# Sheet2.net
KiCad netlist of a schematic drawn in Altium Designer
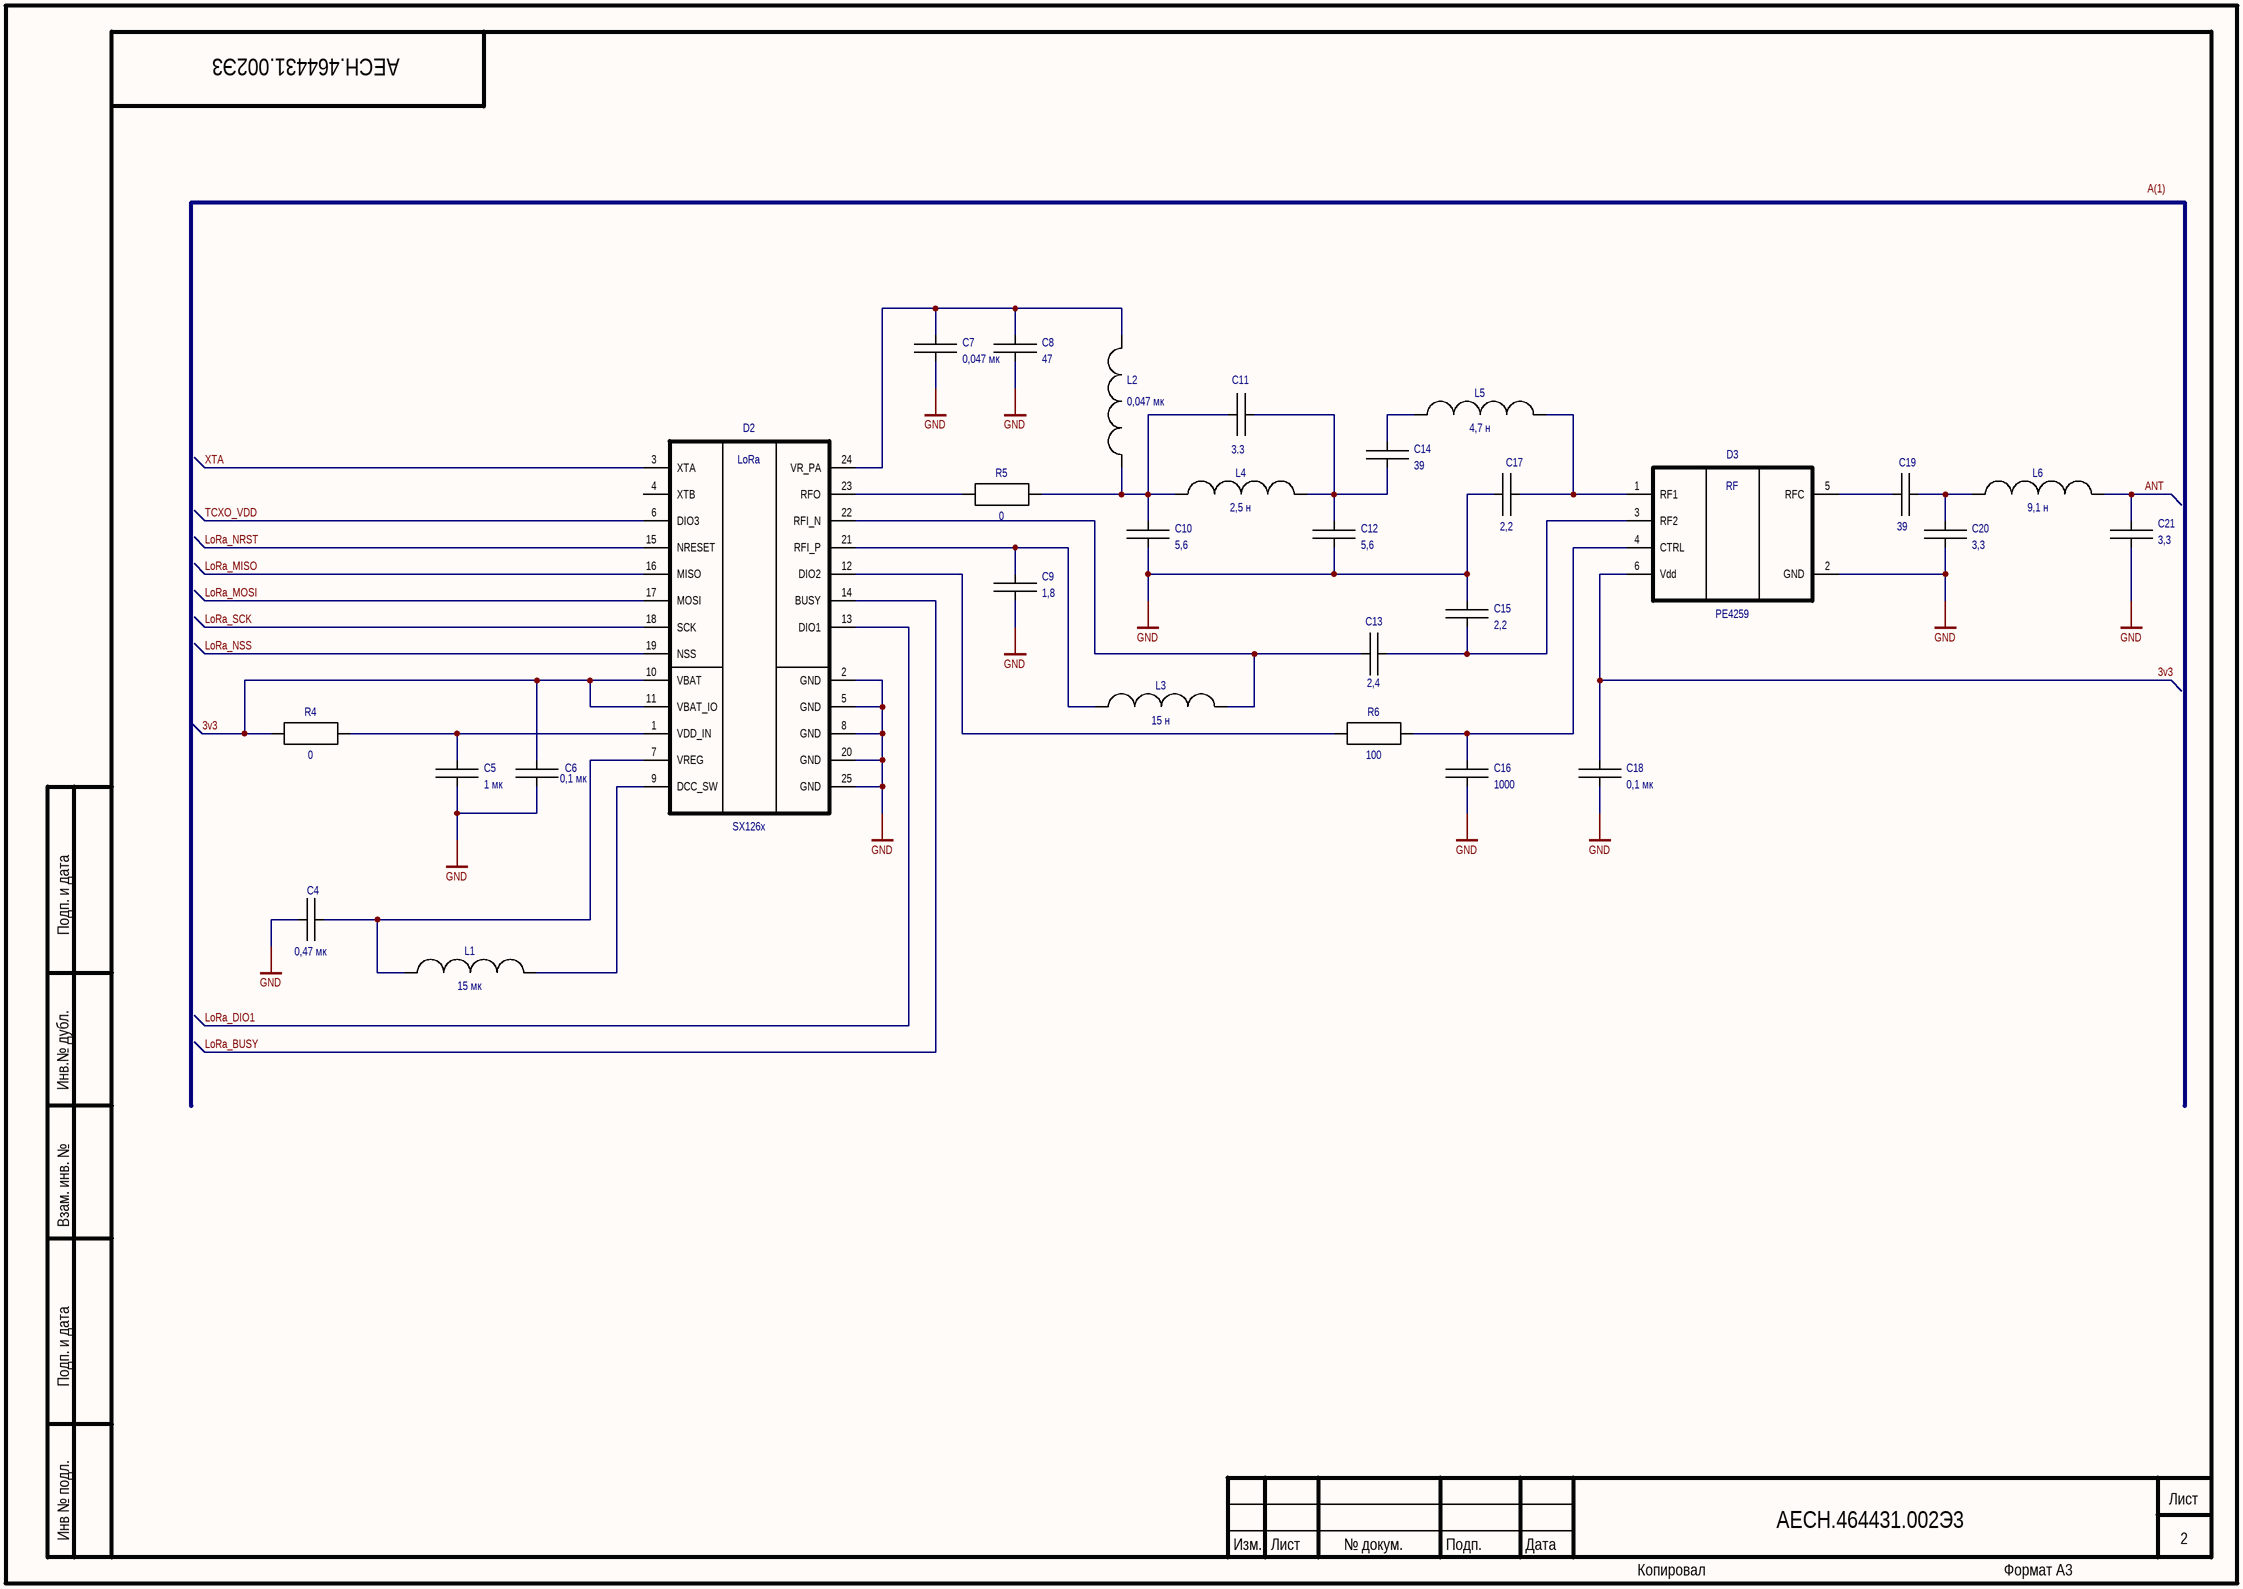
[diagram p0: Sheet2.SchDoc]

(export (version "E")
  (design (tool "Eeschema 10.0.6"))
  (components
    (comp (ref "C4")
      (value "0,47 мк")
      (footprint "С0603")
      (fields (field (name "VOLTAGE") "10 В") (field (name "Comment") "C"))
      (libsource (lib "Schlib1") (part "C"))
    )
    (comp (ref "C5")
      (value "1 мк")
      (footprint "С0603")
      (fields (field (name "VOLTAGE") "10 В") (field (name "Comment") "C"))
      (libsource (lib "Schlib1") (part "C"))
    )
    (comp (ref "C6")
      (value "0,1 мк")
      (footprint "С0603")
      (fields (field (name "VOLTAGE") "16 В") (field (name "Comment") "C"))
      (libsource (lib "Schlib1") (part "C"))
    )
    (comp (ref "C7")
      (value "0,047 мк")
      (footprint "С0603")
      (fields (field (name "VOLTAGE") "16 В") (field (name "Comment") "C"))
      (libsource (lib "Schlib1") (part "C"))
    )
    (comp (ref "C8")
      (value "47")
      (footprint "С0603")
      (fields (field (name "VOLTAGE") "50 В") (field (name "Comment") "C"))
      (libsource (lib "Schlib1") (part "C"))
    )
    (comp (ref "C9")
      (value "1,8")
      (footprint "С0603")
      (fields (field (name "VOLTAGE") "50 В") (field (name "Comment") "C"))
      (libsource (lib "Schlib1") (part "C"))
    )
    (comp (ref "C10")
      (value "5,6")
      (footprint "С0603")
      (fields (field (name "VOLTAGE") "50 В") (field (name "Comment") "C"))
      (libsource (lib "Schlib1") (part "C"))
    )
    (comp (ref "C11")
      (value "3.3")
      (footprint "С0603")
      (fields (field (name "VOLTAGE") "50 В") (field (name "Comment") "C"))
      (libsource (lib "Schlib1") (part "C"))
    )
    (comp (ref "C12")
      (value "5,6")
      (footprint "С0603")
      (fields (field (name "VOLTAGE") "50") (field (name "Comment") "C"))
      (libsource (lib "Schlib1") (part "C"))
    )
    (comp (ref "C13")
      (value "2,4")
      (footprint "С0603")
      (fields (field (name "VOLTAGE") "50 В") (field (name "Comment") "C"))
      (libsource (lib "Schlib1") (part "C"))
    )
    (comp (ref "C14")
      (value "39")
      (footprint "С0603")
      (fields (field (name "VOLTAGE") "50 В") (field (name "Comment") "C"))
      (libsource (lib "Schlib1") (part "C"))
    )
    (comp (ref "C15")
      (value "2,2")
      (footprint "С0603")
      (fields (field (name "VOLTAGE") "50 В") (field (name "Comment") "C"))
      (libsource (lib "Schlib1") (part "C"))
    )
    (comp (ref "C16")
      (value "1000")
      (footprint "С0603")
      (fields (field (name "VOLTAGE") "10 В") (field (name "Comment") "C"))
      (libsource (lib "Schlib1") (part "C"))
    )
    (comp (ref "C17")
      (value "2,2")
      (footprint "С0603")
      (fields (field (name "VOLTAGE") "50 В") (field (name "Comment") "C"))
      (libsource (lib "Schlib1") (part "C"))
    )
    (comp (ref "C18")
      (value "0,1 мк")
      (footprint "С0603")
      (fields (field (name "VOLTAGE") "16 В") (field (name "Comment") "C"))
      (libsource (lib "Schlib1") (part "C"))
    )
    (comp (ref "C19")
      (value "39")
      (footprint "С0603")
      (fields (field (name "VOLTAGE") "50 В") (field (name "Comment") "C"))
      (libsource (lib "Schlib1") (part "C"))
    )
    (comp (ref "C20")
      (value "3,3")
      (footprint "С0603")
      (fields (field (name "VOLTAGE") "50 В") (field (name "Comment") "C"))
      (libsource (lib "Schlib1") (part "C"))
    )
    (comp (ref "C21")
      (value "3,3")
      (footprint "С0603")
      (fields (field (name "VOLTAGE") "50 В") (field (name "Comment") "C"))
      (libsource (lib "Schlib1") (part "C"))
    )
    (comp (ref "D2") (value "SX126x") (footprint "QFN24_4X4_SEM") (libsource (lib "Schlib1") (part "SX126x")))
    (comp (ref "D3") (value "PE4259") (footprint "SC70-6") (libsource (lib "Schlib1") (part "PE4259")))
    (comp (ref "L1")
      (value "15 мк")
      (footprint "IND_0805")
      (fields (field (name "Comment") "L"))
      (libsource (lib "Schlib1") (part "L"))
    )
    (comp (ref "L2")
      (value "0,047 мк")
      (footprint "INDC_0603")
      (fields (field (name "Comment") "L"))
      (libsource (lib "Schlib1") (part "L"))
    )
    (comp (ref "L3")
      (value "15 н")
      (footprint "INDC_0603")
      (fields (field (name "Comment") "L"))
      (libsource (lib "Schlib1") (part "L"))
    )
    (comp (ref "L4")
      (value "2,5 н")
      (footprint "INDC_0603")
      (fields (field (name "Comment") "L"))
      (libsource (lib "Schlib1") (part "L"))
    )
    (comp (ref "L5")
      (value "4,7 н")
      (footprint "INDC_0603")
      (fields (field (name "Comment") "L"))
      (libsource (lib "Schlib1") (part "L"))
    )
    (comp (ref "L6")
      (value "9,1 н")
      (footprint "INDC_0603")
      (fields (field (name "Comment") "L"))
      (libsource (lib "Schlib1") (part "L"))
    )
    (comp (ref "R4")
      (value "0")
      (footprint "R0603")
      (fields (field (name "Comment") "R"))
      (libsource (lib "Schlib1") (part "R"))
    )
    (comp (ref "R5")
      (value "0")
      (footprint "R0603")
      (fields (field (name "Comment") "R"))
      (libsource (lib "Schlib1") (part "R"))
    )
    (comp (ref "R6")
      (value "100")
      (footprint "R0603")
      (fields (field (name "Comment") "R"))
      (libsource (lib "Schlib1") (part "R"))
    )
  )
  (nets
    (net (code "1") (name "/3v3") (class "Default")
      (node (ref "C18") (pin "1") (pinfunction "1_1") (pintype "passive"))
      (node (ref "C6") (pin "1") (pinfunction "1_1") (pintype "passive"))
      (node (ref "D2") (pin "10") (pinfunction "VBAT_10") (pintype "passive"))
      (node (ref "D2") (pin "11") (pinfunction "VBAT_IO_11") (pintype "passive"))
      (node (ref "D3") (pin "6") (pinfunction "Vdd_6") (pintype "passive"))
      (node (ref "R4") (pin "1") (pinfunction "1_1") (pintype "passive"))
    )
    (net (code "3") (name "/ANT") (class "Default")
      (node (ref "C21") (pin "1") (pinfunction "1_1") (pintype "passive"))
      (node (ref "L6") (pin "2") (pinfunction "2_2") (pintype "passive"))
    )
    (net (code "4") (name "/LoRa_BUSY") (class "Default")
      (node (ref "D2") (pin "14") (pinfunction "BUSY_14") (pintype "passive"))
    )
    (net (code "5") (name "/LoRa_DIO1") (class "Default")
      (node (ref "D2") (pin "13") (pinfunction "DIO1_13") (pintype "passive"))
    )
    (net (code "6") (name "/LoRa_MISO") (class "Default")
      (node (ref "D2") (pin "16") (pinfunction "MISO_16") (pintype "passive"))
    )
    (net (code "7") (name "/LoRa_MOSI") (class "Default")
      (node (ref "D2") (pin "17") (pinfunction "MOSI_17") (pintype "passive"))
    )
    (net (code "8") (name "/LoRa_NRST") (class "Default")
      (node (ref "D2") (pin "15") (pinfunction "NRESET_15") (pintype "passive"))
    )
    (net (code "9") (name "/LoRa_NSS") (class "Default")
      (node (ref "D2") (pin "19") (pinfunction "NSS_19") (pintype "passive"))
    )
    (net (code "10") (name "/LoRa_SCK") (class "Default")
      (node (ref "D2") (pin "18") (pinfunction "SCK_18") (pintype "passive"))
    )
    (net (code "11") (name "/TCXO_VDD") (class "Default")
      (node (ref "D2") (pin "6") (pinfunction "DIO3_6") (pintype "passive"))
    )
    (net (code "12") (name "/XTA") (class "Default")
      (node (ref "D2") (pin "3") (pinfunction "XTA_3") (pintype "passive"))
    )
    (net (code "13") (name "GND") (class "Default")
      (node (ref "C10") (pin "2") (pinfunction "2_2") (pintype "passive"))
      (node (ref "C12") (pin "2") (pinfunction "2_2") (pintype "passive"))
      (node (ref "C15") (pin "1") (pinfunction "1_1") (pintype "passive"))
      (node (ref "C16") (pin "2") (pinfunction "2_2") (pintype "passive"))
      (node (ref "C17") (pin "1") (pinfunction "1_1") (pintype "passive"))
      (node (ref "C18") (pin "2") (pinfunction "2_2") (pintype "passive"))
      (node (ref "C20") (pin "2") (pinfunction "2_2") (pintype "passive"))
      (node (ref "C21") (pin "2") (pinfunction "2_2") (pintype "passive"))
      (node (ref "C4") (pin "1") (pinfunction "1_1") (pintype "passive"))
      (node (ref "C5") (pin "2") (pinfunction "2_2") (pintype "passive"))
      (node (ref "C6") (pin "2") (pinfunction "2_2") (pintype "passive"))
      (node (ref "C7") (pin "2") (pinfunction "2_2") (pintype "passive"))
      (node (ref "C8") (pin "2") (pinfunction "2_2") (pintype "passive"))
      (node (ref "C9") (pin "2") (pinfunction "2_2") (pintype "passive"))
      (node (ref "D2") (pin "2") (pinfunction "GND_2") (pintype "passive"))
      (node (ref "D2") (pin "20") (pinfunction "GND_20") (pintype "passive"))
      (node (ref "D2") (pin "25") (pinfunction "GND_25") (pintype "passive"))
      (node (ref "D2") (pin "5") (pinfunction "GND_5") (pintype "passive"))
      (node (ref "D2") (pin "8") (pinfunction "GND_8") (pintype "passive"))
      (node (ref "D3") (pin "2") (pinfunction "GND_2") (pintype "passive"))
    )
    (net (code "14") (name "Net-(C10-Pad1)") (class "Default")
      (node (ref "C10") (pin "1") (pinfunction "1_1") (pintype "passive"))
      (node (ref "C11") (pin "1") (pinfunction "1_1") (pintype "passive"))
      (node (ref "L2") (pin "1") (pinfunction "1_1") (pintype "passive"))
      (node (ref "L4") (pin "1") (pinfunction "1_1") (pintype "passive"))
      (node (ref "R5") (pin "2") (pinfunction "2_2") (pintype "passive"))
    )
    (net (code "15") (name "Net-(C11-Pad2)") (class "Default")
      (node (ref "C11") (pin "2") (pinfunction "2_2") (pintype "passive"))
      (node (ref "C12") (pin "1") (pinfunction "1_1") (pintype "passive"))
      (node (ref "C14") (pin "1") (pinfunction "1_1") (pintype "passive"))
      (node (ref "L4") (pin "2") (pinfunction "2_2") (pintype "passive"))
    )
    (net (code "16") (name "Net-(C14-Pad2)") (class "Default")
      (node (ref "C14") (pin "2") (pinfunction "2_2") (pintype "passive"))
      (node (ref "L5") (pin "1") (pinfunction "1_1") (pintype "passive"))
    )
    (net (code "17") (name "Net-(C19-Pad2)") (class "Default")
      (node (ref "C19") (pin "2") (pinfunction "2_2") (pintype "passive"))
      (node (ref "C20") (pin "1") (pinfunction "1_1") (pintype "passive"))
      (node (ref "L6") (pin "1") (pinfunction "1_1") (pintype "passive"))
    )
    (net (code "18") (name "Net-(D2-DCC_SW)") (class "Default")
      (node (ref "D2") (pin "9") (pinfunction "DCC_SW_9") (pintype "passive"))
      (node (ref "L1") (pin "2") (pinfunction "2_2") (pintype "passive"))
    )
    (net (code "19") (name "Net-(D2-DIO2)") (class "Default")
      (node (ref "D2") (pin "12") (pinfunction "DIO2_12") (pintype "passive"))
      (node (ref "R6") (pin "1") (pinfunction "1_1") (pintype "passive"))
    )
    (net (code "20") (name "Net-(D2-RFI_N)") (class "Default")
      (node (ref "C13") (pin "1") (pinfunction "1_1") (pintype "passive"))
      (node (ref "D2") (pin "22") (pinfunction "RFI_N_22") (pintype "passive"))
      (node (ref "L3") (pin "2") (pinfunction "2_2") (pintype "passive"))
    )
    (net (code "21") (name "Net-(D2-RFI_P)") (class "Default")
      (node (ref "C9") (pin "1") (pinfunction "1_1") (pintype "passive"))
      (node (ref "D2") (pin "21") (pinfunction "RFI_P_21") (pintype "passive"))
      (node (ref "L3") (pin "1") (pinfunction "1_1") (pintype "passive"))
    )
    (net (code "22") (name "Net-(D2-RFO)") (class "Default")
      (node (ref "D2") (pin "23") (pinfunction "RFO_23") (pintype "passive"))
      (node (ref "R5") (pin "1") (pinfunction "1_1") (pintype "passive"))
    )
    (net (code "23") (name "Net-(D2-VDD_IN)") (class "Default")
      (node (ref "C5") (pin "1") (pinfunction "1_1") (pintype "passive"))
      (node (ref "D2") (pin "1") (pinfunction "VDD_IN_1") (pintype "passive"))
      (node (ref "R4") (pin "2") (pinfunction "2_2") (pintype "passive"))
    )
    (net (code "24") (name "Net-(D2-VREG)") (class "Default")
      (node (ref "C4") (pin "2") (pinfunction "2_2") (pintype "passive"))
      (node (ref "D2") (pin "7") (pinfunction "VREG_7") (pintype "passive"))
      (node (ref "L1") (pin "1") (pinfunction "1_1") (pintype "passive"))
    )
    (net (code "25") (name "Net-(D2-VR_PA)") (class "Default")
      (node (ref "C7") (pin "1") (pinfunction "1_1") (pintype "passive"))
      (node (ref "C8") (pin "1") (pinfunction "1_1") (pintype "passive"))
      (node (ref "D2") (pin "24") (pinfunction "VR_PA_24") (pintype "passive"))
      (node (ref "L2") (pin "2") (pinfunction "2_2") (pintype "passive"))
    )
    (net (code "26") (name "Net-(D3-CTRL)") (class "Default")
      (node (ref "C16") (pin "1") (pinfunction "1_1") (pintype "passive"))
      (node (ref "D3") (pin "4") (pinfunction "CTRL_4") (pintype "passive"))
      (node (ref "R6") (pin "2") (pinfunction "2_2") (pintype "passive"))
    )
    (net (code "27") (name "Net-(D3-RF1)") (class "Default")
      (node (ref "C17") (pin "2") (pinfunction "2_2") (pintype "passive"))
      (node (ref "D3") (pin "1") (pinfunction "RF1_1") (pintype "passive"))
      (node (ref "L5") (pin "2") (pinfunction "2_2") (pintype "passive"))
    )
    (net (code "28") (name "Net-(D3-RF2)") (class "Default")
      (node (ref "C13") (pin "2") (pinfunction "2_2") (pintype "passive"))
      (node (ref "C15") (pin "2") (pinfunction "2_2") (pintype "passive"))
      (node (ref "D3") (pin "3") (pinfunction "RF2_3") (pintype "passive"))
    )
    (net (code "29") (name "Net-(D3-RFC)") (class "Default")
      (node (ref "C19") (pin "1") (pinfunction "1_1") (pintype "passive"))
      (node (ref "D3") (pin "5") (pinfunction "RFC_5") (pintype "passive"))
    )
    (net (code "30") (name "unconnected-(D2-XTB-Pad4)") (class "Default")
      (node (ref "D2") (pin "4") (pinfunction "XTB_4") (pintype "passive"))
    )
  )
)
